# DC-DC_14V.net
KiCad netlist of a schematic drawn in Altium Designer
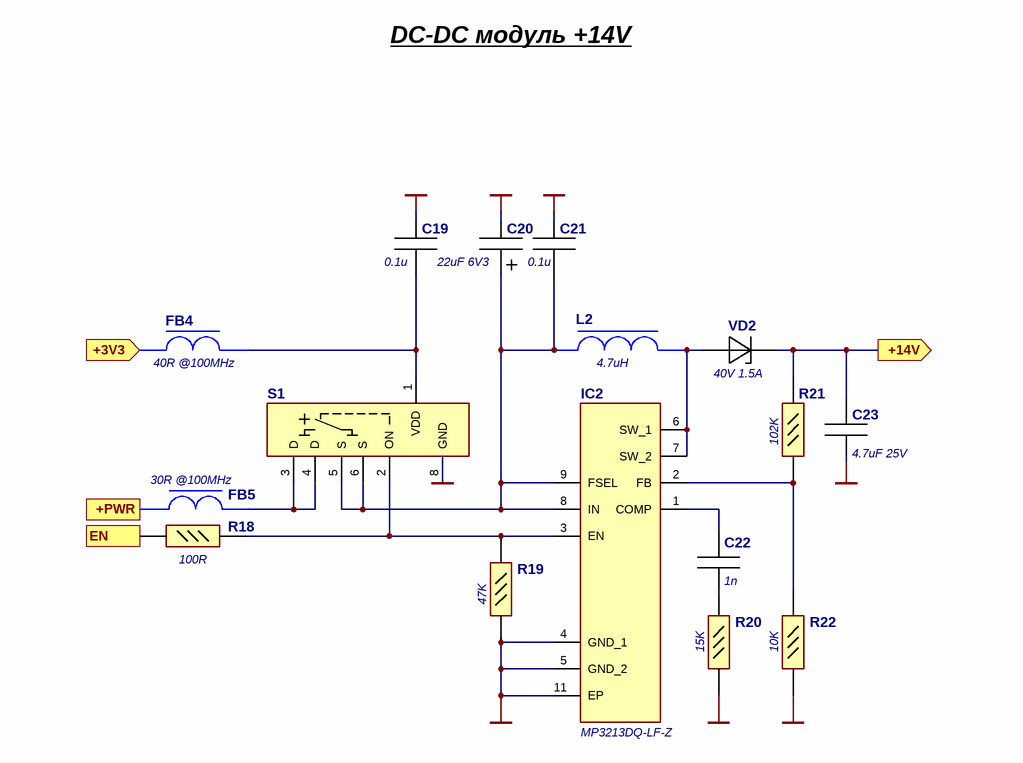
[diagram p0: DC-DC модуль +14V.SchDoc]

(export (version "E")
  (design (tool "Eeschema 10.0.6"))
  (components
    (comp (ref "C19")
      (value "0.1u")
      (footprint ":CAP0402 100x50x50")
      (description "±10% 25V Ceramic Capacitor X7R 0402 (1005 Metric)")
      (fields
        (field (name "MANUFACTURER_PART_NUMBER") "GRM155R71E104KE14J")
        (field (name "MOUSER PART NUMBER") "81-GRM155R71E104KE4J")
      )
      (libsource (lib "Capacitors 0402") (part "GRM155R71E104KE14J"))
    )
    (comp (ref "C20")
      (value "22uF 6V3")
      (footprint ":CAP1206 C3216-18")
      (description "22uF Molded Tantalum Capacitors 6.3V 1206 (3216 Metric) 300mOhm @ 100kHz")
      (fields (field (name "MANUFACTURER_PART_NUMBER") "TPSA226K006R0300"))
      (libsource (lib "Capacitors 1206") (part "TPSA226K006R0300"))
    )
    (comp (ref "C21")
      (value "0.1u")
      (footprint ":CAP0402 100x50x50")
      (description "±10% 25V Ceramic Capacitor X7R 0402 (1005 Metric)")
      (fields
        (field (name "MANUFACTURER_PART_NUMBER") "GRM155R71E104KE14J")
        (field (name "MOUSER PART NUMBER") "81-GRM155R71E104KE4J")
      )
      (libsource (lib "Capacitors 0402") (part "GRM155R71E104KE14J"))
    )
    (comp (ref "C22")
      (value "1n")
      (footprint ":CAP0402 100x50x50")
      (description "±5% 50V Ceramic Capacitor C0G, NP0 0402 (1005 Metric)")
      (fields (field (name "MANUFACTURER_PART_NUMBER") "GRM1555C1H102JA01J"))
      (libsource (lib "Capacitors 0402") (part "GRM1555C1H102JA01J"))
    )
    (comp (ref "C23")
      (value "4.7uF 25V")
      (footprint ":CAP0805 C2012X125")
      (description "CAP CER 4.7uF 25V X7R 0805")
      (fields (field (name "MANUFACTURER_PART_NUMBER") "GRM21BZ71E475KE15L"))
      (libsource (lib "Capacitors 0805") (part "GRM21BZ71E475KE15L"))
    )
    (comp (ref "FB4")
      (value "40R @100MHz")
      (footprint ":FER MMZ1005Y400CTD25")
      (description "40 Ohms @ 100MHz 1 Signal Line Ferrite Bead 0402 (1005 Metric) 550mA 100mOhm")
      (fields
        (field (name "MANUFACTURER_PART_NUMBER") "MMZ1005Y400CTD25")
        (field (name "MOUSER PART NUMBER") "810-MMZ1005Y400CTD25")
      )
      (libsource (lib "Ferrite Bead") (part "MMZ1005Y400CTD25"))
    )
    (comp (ref "FB5")
      (value "30R @100MHz")
      (footprint ":FER BLM18SP300SN1D")
      (description "30 Ohms @ 100MHz 1 Power Line Ferrite Bead 0603 (1608 Metric) 6A 8mOhm")
      (fields
        (field (name "MANUFACTURER_PART_NUMBER") "BLM18SP300SN1D")
        (field (name "MOUSER PART NUMBER") "81-BLM18SP300SN1D")
      )
      (libsource (lib "Ferrite Bead") (part "BLM18SP300SN1D"))
    )
    (comp (ref "IC2")
      (value "MP3213DQ-LF-Z")
      (footprint ":QFN10 P300X300X100-11N-D")
      (description "DC/DC Converter \r\n3...22V 3.5A")
      (fields (field (name "MOUSER PART NUMBER") "946-MP3213DQLFZ"))
      (libsource (lib "DC-DC convertors") (part "MP3213DQ-LF-Z"))
    )
    (comp (ref "L2")
      (value "4.7uH")
      (footprint ":IND1210 C3225")
      (fields (field (name "MANUFACTURER_PART_NUMBER") "CBC3225T4R7MR"))
      (libsource (lib "Inductance") (part "CBC3225T4R7MR"))
    )
    (comp (ref "R18")
      (value "RC0402FR-07")
      (footprint ":RES0402")
      (fields (field (name "MANUFACTURER_PART_NUMBER (PART 2: VALUE)") "100R"))
      (libsource (lib "Resistors 0402") (part "RC0402FR-07"))
    )
    (comp (ref "R19")
      (value "RC0402FR-07")
      (footprint ":RES0402")
      (fields (field (name "MANUFACTURER_PART_NUMBER (PART 2: VALUE)") "47K"))
      (libsource (lib "") (part "RC0402FR-07_1"))
    )
    (comp (ref "R20")
      (value "RC0402FR-07")
      (footprint ":RES0402")
      (fields (field (name "MANUFACTURER_PART_NUMBER (PART 2: VALUE)") "15K"))
      (libsource (lib "") (part "RC0402FR-07_1"))
    )
    (comp (ref "R21")
      (value "RC0402FR-07")
      (footprint ":RES0402")
      (fields (field (name "MANUFACTURER_PART_NUMBER (PART 2: VALUE)") "102K"))
      (libsource (lib "") (part "RC0402FR-07_1"))
    )
    (comp (ref "R22")
      (value "RC0402FR-07")
      (footprint ":RES0402")
      (fields (field (name "MANUFACTURER_PART_NUMBER (PART 2: VALUE)") "10K"))
      (libsource (lib "") (part "RC0402FR-07_1"))
    )
    (comp (ref "S1")
      (value "4A 7.8mOhm")
      (footprint ":TRAN SLG59M309V")
      (description "Power Switch/Driver 1:1 N-Channel 4A  7.8mOhm 8-FC-TDFN (1.5x2)")
      (fields (field (name "MANUFACTURER_PART_NUMBER") "SLG59M309V"))
      (libsource (lib "Switching and Relays") (part "SLG59M309V"))
    )
    (comp (ref "VD2")
      (value "40V 1.5A")
      (footprint ":DIODE CST2C")
      (description "Diode Schottky 40V 1.5A\r\n@If 550mV @ 1.5A\r\n@Vr 200µA @ 40V")
      (fields (field (name "MANUFACTURER_PART_NUMBER") "CCS15S40,L3F"))
      (libsource (lib "Diodes 0603") (part "CCS15S40,L3F"))
    )
  )
  (nets
    (net (code "1") (name "/+3V3") (class "Default")
      (node (ref "FB4") (pin "2") (pinfunction "2_2") (pintype "passive"))
    )
    (net (code "2") (name "/+14V") (class "Default")
      (node (ref "C23") (pin "2") (pinfunction "2_2") (pintype "passive"))
      (node (ref "R21") (pin "2") (pinfunction "2_2") (pintype "passive"))
      (node (ref "VD2") (pin "1") (pinfunction "K_1") (pintype "passive"))
    )
    (net (code "3") (name "/+PWR") (class "Default")
      (node (ref "FB5") (pin "1") (pinfunction "1_1") (pintype "passive"))
    )
    (net (code "4") (name "/EN") (class "Default")
      (node (ref "R18") (pin "1") (pinfunction "1_1") (pintype "passive"))
    )
    (net (code "5") (name "GND") (class "Default")
      (node (ref "C19") (pin "1") (pinfunction "1_1") (pintype "passive"))
      (node (ref "C20") (pin "2") (pinfunction "2_2") (pintype "passive"))
      (node (ref "C21") (pin "1") (pinfunction "1_1") (pintype "passive"))
      (node (ref "C23") (pin "1") (pinfunction "1_1") (pintype "passive"))
      (node (ref "IC2") (pin "11") (pinfunction "EP_11") (pintype "passive"))
      (node (ref "IC2") (pin "4") (pinfunction "GND_1_4") (pintype "passive"))
      (node (ref "IC2") (pin "5") (pinfunction "GND_2_5") (pintype "passive"))
      (node (ref "R19") (pin "1") (pinfunction "1_1") (pintype "passive"))
      (node (ref "R20") (pin "1") (pinfunction "1_1") (pintype "passive"))
      (node (ref "R22") (pin "1") (pinfunction "1_1") (pintype "passive"))
      (node (ref "S1") (pin "8") (pinfunction "GND_8") (pintype "passive"))
    )
    (net (code "6") (name "Net-(C20-+)") (class "Default")
      (node (ref "C20") (pin "1") (pinfunction "+_1") (pintype "passive"))
      (node (ref "C21") (pin "2") (pinfunction "2_2") (pintype "passive"))
      (node (ref "IC2") (pin "8") (pinfunction "IN_8") (pintype "passive"))
      (node (ref "IC2") (pin "9") (pinfunction "FSEL_9") (pintype "passive"))
      (node (ref "L2") (pin "1") (pinfunction "1_1") (pintype "passive"))
      (node (ref "S1") (pin "5") (pinfunction "S_5") (pintype "passive"))
      (node (ref "S1") (pin "6") (pinfunction "S_6") (pintype "passive"))
    )
    (net (code "7") (name "Net-(C22-Pad1)") (class "Default")
      (node (ref "C22") (pin "1") (pinfunction "1_1") (pintype "passive"))
      (node (ref "R20") (pin "2") (pinfunction "2_2") (pintype "passive"))
    )
    (net (code "8") (name "Net-(FB5-Pad2)") (class "Default")
      (node (ref "FB5") (pin "2") (pinfunction "2_2") (pintype "passive"))
      (node (ref "S1") (pin "3") (pinfunction "D_3") (pintype "passive"))
      (node (ref "S1") (pin "4") (pinfunction "D_4") (pintype "passive"))
    )
    (net (code "9") (name "Net-(IC2-COMP)") (class "Default")
      (node (ref "C22") (pin "2") (pinfunction "2_2") (pintype "passive"))
      (node (ref "IC2") (pin "1") (pinfunction "COMP_1") (pintype "passive"))
    )
    (net (code "10") (name "Net-(IC2-EN)") (class "Default")
      (node (ref "IC2") (pin "3") (pinfunction "EN_3") (pintype "passive"))
      (node (ref "R18") (pin "2") (pinfunction "2_2") (pintype "passive"))
      (node (ref "R19") (pin "2") (pinfunction "2_2") (pintype "passive"))
      (node (ref "S1") (pin "2") (pinfunction "ON_2") (pintype "passive"))
    )
    (net (code "11") (name "Net-(IC2-FB)") (class "Default")
      (node (ref "IC2") (pin "2") (pinfunction "FB_2") (pintype "passive"))
      (node (ref "R21") (pin "1") (pinfunction "1_1") (pintype "passive"))
      (node (ref "R22") (pin "2") (pinfunction "2_2") (pintype "passive"))
    )
    (net (code "12") (name "Net-(IC2-SW_1)") (class "Default")
      (node (ref "IC2") (pin "6") (pinfunction "SW_1_6") (pintype "passive"))
      (node (ref "IC2") (pin "7") (pinfunction "SW_2_7") (pintype "passive"))
      (node (ref "L2") (pin "2") (pinfunction "2_2") (pintype "passive"))
      (node (ref "VD2") (pin "2") (pinfunction "A_2") (pintype "passive"))
    )
    (net (code "13") (name "Net-(S1-VDD)") (class "Default")
      (node (ref "C19") (pin "2") (pinfunction "2_2") (pintype "passive"))
      (node (ref "FB4") (pin "1") (pinfunction "1_1") (pintype "passive"))
      (node (ref "S1") (pin "1") (pinfunction "VDD_1") (pintype "passive"))
    )
  )
)
